# Sensor_Filters.net
KiCad netlist of a schematic drawn in Altium Designer
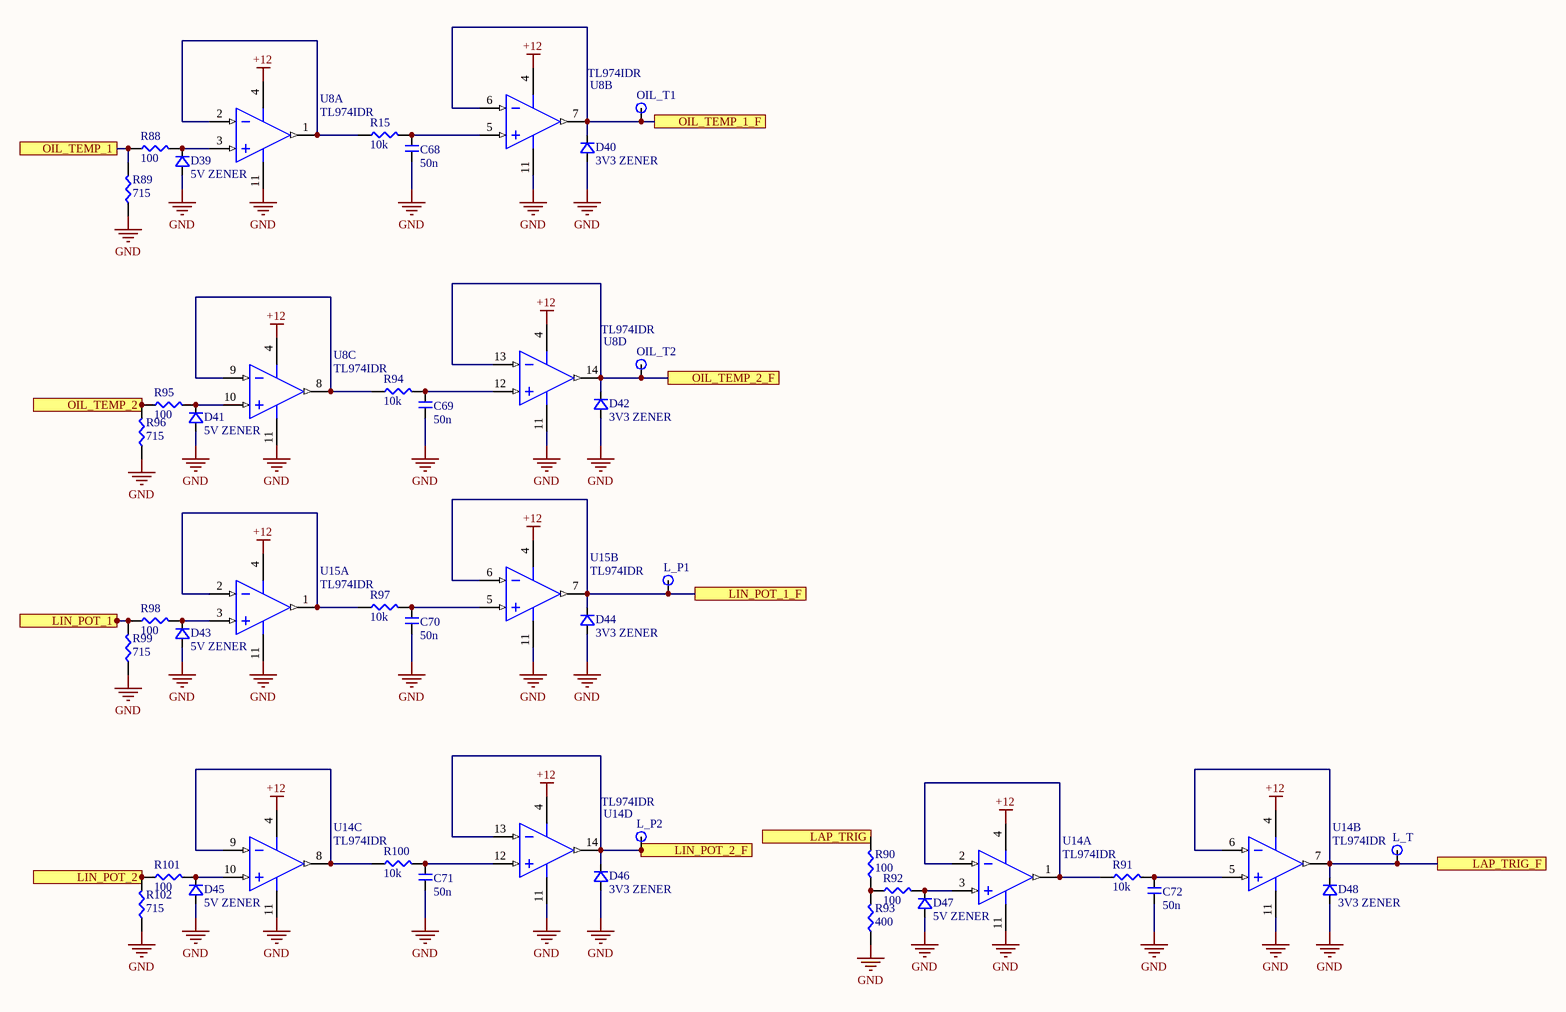
[diagram p0: Sensor_Filters.SchDoc]

(export (version "E")
  (design (tool "Eeschema 10.0.6"))
  (components
    (comp (ref "C68")
      (value "50n")
      (footprint "CAP-0603")
      (fields (field (name "SOURCE") "ife19_Elec_Library.SchLib"))
      (libsource (lib "Illini Formula Electric") (part "CAP-0603"))
    )
    (comp (ref "C69")
      (value "50n")
      (footprint "CAP-0603")
      (fields (field (name "SOURCE") "ife19_Elec_Library.SchLib"))
      (libsource (lib "Illini Formula Electric") (part "CAP-0603"))
    )
    (comp (ref "C70")
      (value "50n")
      (footprint "CAP-0603")
      (fields (field (name "SOURCE") "ife19_Elec_Library.SchLib"))
      (libsource (lib "Illini Formula Electric") (part "CAP-0603"))
    )
    (comp (ref "C71")
      (value "50n")
      (footprint "CAP-0603")
      (fields (field (name "SOURCE") "ife19_Elec_Library.SchLib"))
      (libsource (lib "Illini Formula Electric") (part "CAP-0603"))
    )
    (comp (ref "C72")
      (value "50n")
      (footprint "CAP-0603")
      (fields (field (name "SOURCE") "ife19_Elec_Library.SchLib"))
      (libsource (lib "Illini Formula Electric") (part "CAP-0603"))
    )
    (comp (ref "D39")
      (value "5V ZENER")
      (footprint "SOD123")
      (fields (field (name "SOURCE") "ife19_Elec_Library.SchLib"))
      (libsource (lib "") (part "Symbol_1"))
    )
    (comp (ref "D40")
      (value "3V3 ZENER")
      (footprint "SOD123")
      (fields (field (name "SOURCE") "ife19_Elec_Library.SchLib"))
      (libsource (lib "") (part "Symbol_1"))
    )
    (comp (ref "D41")
      (value "5V ZENER")
      (footprint "SOD123")
      (fields (field (name "SOURCE") "ife19_Elec_Library.SchLib"))
      (libsource (lib "") (part "Symbol_1"))
    )
    (comp (ref "D42")
      (value "3V3 ZENER")
      (footprint "SOD123")
      (fields (field (name "SOURCE") "ife19_Elec_Library.SchLib"))
      (libsource (lib "") (part "Symbol_1"))
    )
    (comp (ref "D43")
      (value "5V ZENER")
      (footprint "SOD123")
      (fields (field (name "SOURCE") "ife19_Elec_Library.SchLib"))
      (libsource (lib "") (part "Symbol_1"))
    )
    (comp (ref "D44")
      (value "3V3 ZENER")
      (footprint "SOD123")
      (fields (field (name "SOURCE") "ife19_Elec_Library.SchLib"))
      (libsource (lib "") (part "Symbol_1"))
    )
    (comp (ref "D45")
      (value "5V ZENER")
      (footprint "SOD123")
      (fields (field (name "SOURCE") "ife19_Elec_Library.SchLib"))
      (libsource (lib "") (part "Symbol_1"))
    )
    (comp (ref "D46")
      (value "3V3 ZENER")
      (footprint "SOD123")
      (fields (field (name "SOURCE") "ife19_Elec_Library.SchLib"))
      (libsource (lib "") (part "Symbol_1"))
    )
    (comp (ref "D47")
      (value "5V ZENER")
      (footprint "SOD123")
      (fields (field (name "SOURCE") "ife19_Elec_Library.SchLib"))
      (libsource (lib "") (part "Symbol_1"))
    )
    (comp (ref "D48")
      (value "3V3 ZENER")
      (footprint "SOD123")
      (fields (field (name "SOURCE") "ife19_Elec_Library.SchLib"))
      (libsource (lib "") (part "Symbol_1"))
    )
    (comp (ref "L_P1")
      (value "~")
      (footprint "Testpoint")
      (fields (field (name "SOURCE") "ife19_Elec_Library.SchLib"))
      (libsource (lib "Illini Formula Electric") (part "Testpoint"))
    )
    (comp (ref "L_P2")
      (value "~")
      (footprint "Testpoint")
      (fields (field (name "SOURCE") "ife19_Elec_Library.SchLib"))
      (libsource (lib "Illini Formula Electric") (part "Testpoint"))
    )
    (comp (ref "L_T")
      (value "~")
      (footprint "Testpoint")
      (fields (field (name "SOURCE") "ife19_Elec_Library.SchLib"))
      (libsource (lib "Illini Formula Electric") (part "Testpoint"))
    )
    (comp (ref "OIL_T1")
      (value "~")
      (footprint "Testpoint")
      (fields (field (name "SOURCE") "ife19_Elec_Library.SchLib"))
      (libsource (lib "Illini Formula Electric") (part "Testpoint"))
    )
    (comp (ref "OIL_T2")
      (value "~")
      (footprint "Testpoint")
      (fields (field (name "SOURCE") "ife19_Elec_Library.SchLib"))
      (libsource (lib "Illini Formula Electric") (part "Testpoint"))
    )
    (comp (ref "R15")
      (value "10k")
      (footprint "RES-0603")
      (fields (field (name "SOURCE") "ife19_Elec_Library.SchLib"))
      (libsource (lib "Illini Formula Electric") (part "Symbol"))
    )
    (comp (ref "R88")
      (value "100")
      (footprint "RES-0603")
      (fields (field (name "SOURCE") "ife19_Elec_Library.SchLib"))
      (libsource (lib "Illini Formula Electric") (part "Symbol"))
    )
    (comp (ref "R89")
      (value "715")
      (footprint "RES-0603")
      (fields (field (name "SOURCE") "ife19_Elec_Library.SchLib"))
      (libsource (lib "Illini Formula Electric") (part "Symbol"))
    )
    (comp (ref "R90")
      (value "100")
      (footprint "RES-0603")
      (fields (field (name "SOURCE") "ife19_Elec_Library.SchLib"))
      (libsource (lib "Illini Formula Electric") (part "Symbol"))
    )
    (comp (ref "R91")
      (value "10k")
      (footprint "RES-0603")
      (fields (field (name "SOURCE") "ife19_Elec_Library.SchLib"))
      (libsource (lib "Illini Formula Electric") (part "Symbol"))
    )
    (comp (ref "R92")
      (value "100")
      (footprint "RES-0603")
      (fields (field (name "SOURCE") "ife19_Elec_Library.SchLib"))
      (libsource (lib "Illini Formula Electric") (part "Symbol"))
    )
    (comp (ref "R93")
      (value "400")
      (footprint "RES-0603")
      (fields (field (name "SOURCE") "ife19_Elec_Library.SchLib"))
      (libsource (lib "Illini Formula Electric") (part "Symbol"))
    )
    (comp (ref "R94")
      (value "10k")
      (footprint "RES-0603")
      (fields (field (name "SOURCE") "ife19_Elec_Library.SchLib"))
      (libsource (lib "Illini Formula Electric") (part "Symbol"))
    )
    (comp (ref "R95")
      (value "100")
      (footprint "RES-0603")
      (fields (field (name "SOURCE") "ife19_Elec_Library.SchLib"))
      (libsource (lib "Illini Formula Electric") (part "Symbol"))
    )
    (comp (ref "R96")
      (value "715")
      (footprint "RES-0603")
      (fields (field (name "SOURCE") "ife19_Elec_Library.SchLib"))
      (libsource (lib "Illini Formula Electric") (part "Symbol"))
    )
    (comp (ref "R97")
      (value "10k")
      (footprint "RES-0603")
      (fields (field (name "SOURCE") "ife19_Elec_Library.SchLib"))
      (libsource (lib "Illini Formula Electric") (part "Symbol"))
    )
    (comp (ref "R98")
      (value "100")
      (footprint "RES-0603")
      (fields (field (name "SOURCE") "ife19_Elec_Library.SchLib"))
      (libsource (lib "Illini Formula Electric") (part "Symbol"))
    )
    (comp (ref "R99")
      (value "715")
      (footprint "RES-0603")
      (fields (field (name "SOURCE") "ife19_Elec_Library.SchLib"))
      (libsource (lib "Illini Formula Electric") (part "Symbol"))
    )
    (comp (ref "R100")
      (value "10k")
      (footprint "RES-0603")
      (fields (field (name "SOURCE") "ife19_Elec_Library.SchLib"))
      (libsource (lib "Illini Formula Electric") (part "Symbol"))
    )
    (comp (ref "R101")
      (value "100")
      (footprint "RES-0603")
      (fields (field (name "SOURCE") "ife19_Elec_Library.SchLib"))
      (libsource (lib "Illini Formula Electric") (part "Symbol"))
    )
    (comp (ref "R102")
      (value "715")
      (footprint "RES-0603")
      (fields (field (name "SOURCE") "ife19_Elec_Library.SchLib"))
      (libsource (lib "Illini Formula Electric") (part "Symbol"))
    )
    (comp (ref "U8")
      (value "TL974IDR")
      (footprint "D0014A_M")
      (fields (field (name "MANUFACTURER") "Texas Instruments"))
      (libsource (lib "Altium Content Vault") (part "TI-TLXX4X_MC3403-X14"))
    )
    (comp (ref "U14")
      (value "TL974IDR")
      (footprint "D0014A_M")
      (fields (field (name "MANUFACTURER") "Texas Instruments"))
      (libsource (lib "Altium Content Vault") (part "TI-TLXX4X_MC3403-X14"))
    )
    (comp (ref "U15")
      (value "TL974IDR")
      (footprint "D0014A_M")
      (fields (field (name "MANUFACTURER") "Texas Instruments"))
      (libsource (lib "Altium Content Vault") (part "TI-TLXX4X_MC3403-X14"))
    )
  )
  (nets
    (net (code "1") (name "+12") (class "Default")
      (node (ref "U14") (pin "4") (pinfunction "VCC+_4") (pintype "power_in"))
      (node (ref "U15") (pin "4") (pinfunction "VCC+_4") (pintype "power_in"))
      (node (ref "U8") (pin "4") (pinfunction "VCC+_4") (pintype "power_in"))
    )
    (net (code "2") (name "/LAP_TRIG") (class "Default")
      (node (ref "R90") (pin "2") (pinfunction "2_2") (pintype "passive"))
    )
    (net (code "3") (name "/LAP_TRIG_F") (class "Default")
      (node (ref "D48") (pin "K") (pinfunction "K_K") (pintype "passive"))
      (node (ref "L_T") (pin "1") (pinfunction "1_1") (pintype "passive"))
      (node (ref "U14") (pin "6") (pinfunction "IN2-_6") (pintype "input"))
      (node (ref "U14") (pin "7") (pinfunction "OUT2_7") (pintype "output"))
    )
    (net (code "4") (name "/LIN_POT_1") (class "Default")
      (node (ref "R98") (pin "1") (pinfunction "1_1") (pintype "passive"))
      (node (ref "R99") (pin "2") (pinfunction "2_2") (pintype "passive"))
    )
    (net (code "5") (name "/LIN_POT_1_F") (class "Default")
      (node (ref "D44") (pin "K") (pinfunction "K_K") (pintype "passive"))
      (node (ref "L_P1") (pin "1") (pinfunction "1_1") (pintype "passive"))
      (node (ref "U15") (pin "6") (pinfunction "IN2-_6") (pintype "input"))
      (node (ref "U15") (pin "7") (pinfunction "OUT2_7") (pintype "output"))
    )
    (net (code "6") (name "/LIN_POT_2") (class "Default")
      (node (ref "R101") (pin "1") (pinfunction "1_1") (pintype "passive"))
      (node (ref "R102") (pin "2") (pinfunction "2_2") (pintype "passive"))
    )
    (net (code "7") (name "/LIN_POT_2_F") (class "Default")
      (node (ref "D46") (pin "K") (pinfunction "K_K") (pintype "passive"))
      (node (ref "L_P2") (pin "1") (pinfunction "1_1") (pintype "passive"))
      (node (ref "U14") (pin "13") (pinfunction "IN4-_13") (pintype "input"))
      (node (ref "U14") (pin "14") (pinfunction "OUT4_14") (pintype "output"))
    )
    (net (code "8") (name "/OIL_TEMP_1") (class "Default")
      (node (ref "R88") (pin "1") (pinfunction "1_1") (pintype "passive"))
      (node (ref "R89") (pin "2") (pinfunction "2_2") (pintype "passive"))
    )
    (net (code "9") (name "/OIL_TEMP_1_F") (class "Default")
      (node (ref "D40") (pin "K") (pinfunction "K_K") (pintype "passive"))
      (node (ref "OIL_T1") (pin "1") (pinfunction "1_1") (pintype "passive"))
      (node (ref "U8") (pin "6") (pinfunction "IN2-_6") (pintype "input"))
      (node (ref "U8") (pin "7") (pinfunction "OUT2_7") (pintype "output"))
    )
    (net (code "10") (name "/OIL_TEMP_2") (class "Default")
      (node (ref "R95") (pin "1") (pinfunction "1_1") (pintype "passive"))
      (node (ref "R96") (pin "2") (pinfunction "2_2") (pintype "passive"))
    )
    (net (code "11") (name "/OIL_TEMP_2_F") (class "Default")
      (node (ref "D42") (pin "K") (pinfunction "K_K") (pintype "passive"))
      (node (ref "OIL_T2") (pin "1") (pinfunction "1_1") (pintype "passive"))
      (node (ref "U8") (pin "13") (pinfunction "IN4-_13") (pintype "input"))
      (node (ref "U8") (pin "14") (pinfunction "OUT4_14") (pintype "output"))
    )
    (net (code "12") (name "GND") (class "Default")
      (node (ref "C68") (pin "1") (pinfunction "1_1") (pintype "passive"))
      (node (ref "C69") (pin "1") (pinfunction "1_1") (pintype "passive"))
      (node (ref "C70") (pin "1") (pinfunction "1_1") (pintype "passive"))
      (node (ref "C71") (pin "1") (pinfunction "1_1") (pintype "passive"))
      (node (ref "C72") (pin "1") (pinfunction "1_1") (pintype "passive"))
      (node (ref "D39") (pin "A") (pinfunction "A_A") (pintype "passive"))
      (node (ref "D40") (pin "A") (pinfunction "A_A") (pintype "passive"))
      (node (ref "D41") (pin "A") (pinfunction "A_A") (pintype "passive"))
      (node (ref "D42") (pin "A") (pinfunction "A_A") (pintype "passive"))
      (node (ref "D43") (pin "A") (pinfunction "A_A") (pintype "passive"))
      (node (ref "D44") (pin "A") (pinfunction "A_A") (pintype "passive"))
      (node (ref "D45") (pin "A") (pinfunction "A_A") (pintype "passive"))
      (node (ref "D46") (pin "A") (pinfunction "A_A") (pintype "passive"))
      (node (ref "D47") (pin "A") (pinfunction "A_A") (pintype "passive"))
      (node (ref "D48") (pin "A") (pinfunction "A_A") (pintype "passive"))
      (node (ref "R102") (pin "1") (pinfunction "1_1") (pintype "passive"))
      (node (ref "R89") (pin "1") (pinfunction "1_1") (pintype "passive"))
      (node (ref "R93") (pin "1") (pinfunction "1_1") (pintype "passive"))
      (node (ref "R96") (pin "1") (pinfunction "1_1") (pintype "passive"))
      (node (ref "R99") (pin "1") (pinfunction "1_1") (pintype "passive"))
      (node (ref "U14") (pin "11") (pinfunction "VCC-_11") (pintype "power_in"))
      (node (ref "U15") (pin "11") (pinfunction "VCC-_11") (pintype "power_in"))
      (node (ref "U8") (pin "11") (pinfunction "VCC-_11") (pintype "power_in"))
    )
    (net (code "13") (name "Net-(R90-Pad1)") (class "Default")
      (node (ref "R90") (pin "1") (pinfunction "1_1") (pintype "passive"))
      (node (ref "R92") (pin "1") (pinfunction "1_1") (pintype "passive"))
      (node (ref "R93") (pin "2") (pinfunction "2_2") (pintype "passive"))
    )
    (net (code "14") (name "Net-(U8A-IN1+)") (class "Default")
      (node (ref "D39") (pin "K") (pinfunction "K_K") (pintype "passive"))
      (node (ref "R88") (pin "2") (pinfunction "2_2") (pintype "passive"))
      (node (ref "U8") (pin "3") (pinfunction "IN1+_3") (pintype "input"))
    )
    (net (code "15") (name "Net-(U8A-IN1-)") (class "Default")
      (node (ref "R15") (pin "1") (pinfunction "1_1") (pintype "passive"))
      (node (ref "U8") (pin "1") (pinfunction "OUT1_1") (pintype "output"))
      (node (ref "U8") (pin "2") (pinfunction "IN1-_2") (pintype "input"))
    )
    (net (code "16") (name "Net-(U8B-IN2+)") (class "Default")
      (node (ref "C68") (pin "2") (pinfunction "2_2") (pintype "passive"))
      (node (ref "R15") (pin "2") (pinfunction "2_2") (pintype "passive"))
      (node (ref "U8") (pin "5") (pinfunction "IN2+_5") (pintype "input"))
    )
    (net (code "17") (name "Net-(U8C-IN3+)") (class "Default")
      (node (ref "D41") (pin "K") (pinfunction "K_K") (pintype "passive"))
      (node (ref "R95") (pin "2") (pinfunction "2_2") (pintype "passive"))
      (node (ref "U8") (pin "10") (pinfunction "IN3+_10") (pintype "input"))
    )
    (net (code "18") (name "Net-(U8C-IN3-)") (class "Default")
      (node (ref "R94") (pin "1") (pinfunction "1_1") (pintype "passive"))
      (node (ref "U8") (pin "8") (pinfunction "OUT3_8") (pintype "output"))
      (node (ref "U8") (pin "9") (pinfunction "IN3-_9") (pintype "input"))
    )
    (net (code "19") (name "Net-(U8D-IN4+)") (class "Default")
      (node (ref "C69") (pin "2") (pinfunction "2_2") (pintype "passive"))
      (node (ref "R94") (pin "2") (pinfunction "2_2") (pintype "passive"))
      (node (ref "U8") (pin "12") (pinfunction "IN4+_12") (pintype "input"))
    )
    (net (code "20") (name "Net-(U14A-IN1+)") (class "Default")
      (node (ref "D47") (pin "K") (pinfunction "K_K") (pintype "passive"))
      (node (ref "R92") (pin "2") (pinfunction "2_2") (pintype "passive"))
      (node (ref "U14") (pin "3") (pinfunction "IN1+_3") (pintype "input"))
    )
    (net (code "21") (name "Net-(U14A-IN1-)") (class "Default")
      (node (ref "R91") (pin "1") (pinfunction "1_1") (pintype "passive"))
      (node (ref "U14") (pin "1") (pinfunction "OUT1_1") (pintype "output"))
      (node (ref "U14") (pin "2") (pinfunction "IN1-_2") (pintype "input"))
    )
    (net (code "22") (name "Net-(U14B-IN2+)") (class "Default")
      (node (ref "C72") (pin "2") (pinfunction "2_2") (pintype "passive"))
      (node (ref "R91") (pin "2") (pinfunction "2_2") (pintype "passive"))
      (node (ref "U14") (pin "5") (pinfunction "IN2+_5") (pintype "input"))
    )
    (net (code "23") (name "Net-(U14C-IN3+)") (class "Default")
      (node (ref "D45") (pin "K") (pinfunction "K_K") (pintype "passive"))
      (node (ref "R101") (pin "2") (pinfunction "2_2") (pintype "passive"))
      (node (ref "U14") (pin "10") (pinfunction "IN3+_10") (pintype "input"))
    )
    (net (code "24") (name "Net-(U14C-IN3-)") (class "Default")
      (node (ref "R100") (pin "1") (pinfunction "1_1") (pintype "passive"))
      (node (ref "U14") (pin "8") (pinfunction "OUT3_8") (pintype "output"))
      (node (ref "U14") (pin "9") (pinfunction "IN3-_9") (pintype "input"))
    )
    (net (code "25") (name "Net-(U14D-IN4+)") (class "Default")
      (node (ref "C71") (pin "2") (pinfunction "2_2") (pintype "passive"))
      (node (ref "R100") (pin "2") (pinfunction "2_2") (pintype "passive"))
      (node (ref "U14") (pin "12") (pinfunction "IN4+_12") (pintype "input"))
    )
    (net (code "26") (name "Net-(U15A-IN1+)") (class "Default")
      (node (ref "D43") (pin "K") (pinfunction "K_K") (pintype "passive"))
      (node (ref "R98") (pin "2") (pinfunction "2_2") (pintype "passive"))
      (node (ref "U15") (pin "3") (pinfunction "IN1+_3") (pintype "input"))
    )
    (net (code "27") (name "Net-(U15A-IN1-)") (class "Default")
      (node (ref "R97") (pin "1") (pinfunction "1_1") (pintype "passive"))
      (node (ref "U15") (pin "1") (pinfunction "OUT1_1") (pintype "output"))
      (node (ref "U15") (pin "2") (pinfunction "IN1-_2") (pintype "input"))
    )
    (net (code "28") (name "Net-(U15B-IN2+)") (class "Default")
      (node (ref "C70") (pin "2") (pinfunction "2_2") (pintype "passive"))
      (node (ref "R97") (pin "2") (pinfunction "2_2") (pintype "passive"))
      (node (ref "U15") (pin "5") (pinfunction "IN2+_5") (pintype "input"))
    )
  )
)
